# esp32.net
KiCad netlist of a schematic drawn in Altium Designer
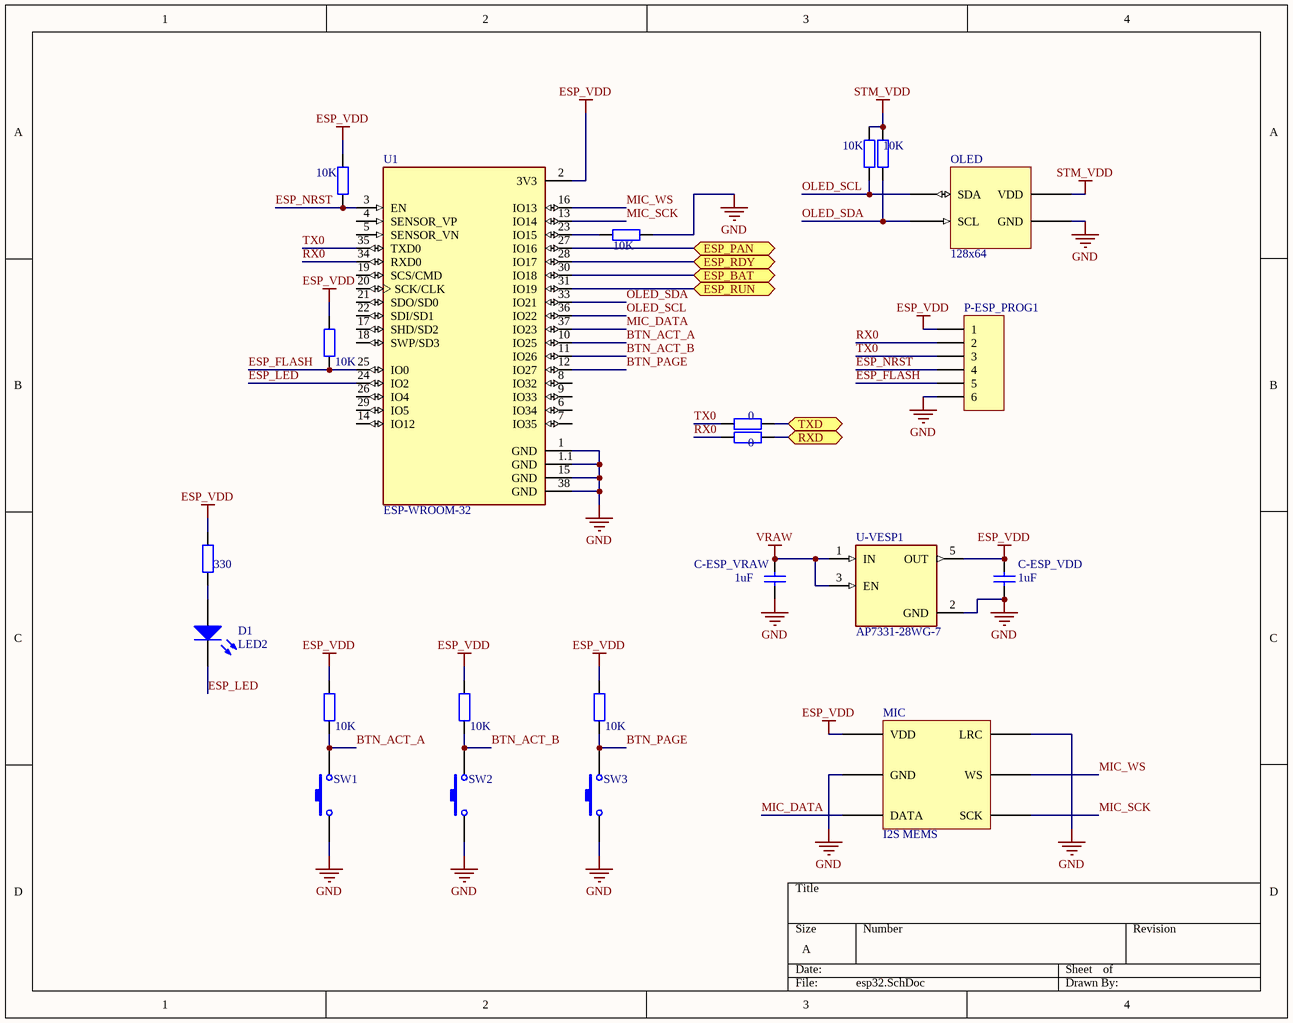
[diagram p0: esp32.SchDoc]

(export (version "E")
  (design (tool "Eeschema 10.0.6"))
  (components
    (comp (ref "C-ESP_VDD")
      (value "1uF")
      (footprint "RAD-0.3")
      (description "Capacitor")
      (fields (field (name "Comment") "Cap") (field (name "PUBLISHER") "Altium Limited"))
      (libsource (lib "Miscellaneous Devices") (part "Cap"))
    )
    (comp (ref "C-ESP_VRAW")
      (value "1uF")
      (footprint "RAD-0.3")
      (description "Capacitor")
      (fields (field (name "Comment") "Cap") (field (name "PUBLISHER") "Altium Limited"))
      (libsource (lib "Miscellaneous Devices") (part "Cap"))
    )
    (comp (ref "D1")
      (value "LED2")
      (footprint "3.2X1.6X1.1")
      (description "Typical RED, GREEN, YELLOW, AMBER GaAs LED")
      (fields (field (name "PUBLISHER") "Altium Limited"))
      (libsource (lib "Miscellaneous Devices") (part "LED2"))
    )
    (comp (ref "MIC") (value "I2S MEMS") (libsource (lib "INMP441") (part "INMP441")))
    (comp (ref "OLED") (value "128x64") (libsource (lib "SH1106") (part "SH1106")))
    (comp (ref "P-ESP_PROG1")
      (value "Header 6")
      (footprint "HDR1X6")
      (description "Header, 6-Pin")
      (fields (field (name "PUBLISHER") "Altium Limited"))
      (libsource (lib "Miscellaneous Connectors") (part "Header 6"))
    )
    (comp (ref "R-BUTTON1")
      (value "10K")
      (footprint "AXIAL-0.4")
      (description "Resistor")
      (fields (field (name "Comment") "Res2") (field (name "PUBLISHER") "Altium Limited"))
      (libsource (lib "Miscellaneous Devices") (part "Res2"))
    )
    (comp (ref "R-BUTTON2")
      (value "10K")
      (footprint "AXIAL-0.4")
      (description "Resistor")
      (fields (field (name "Comment") "Res2") (field (name "PUBLISHER") "Altium Limited"))
      (libsource (lib "Miscellaneous Devices") (part "Res2"))
    )
    (comp (ref "R-BUTTON3")
      (value "10K")
      (footprint "AXIAL-0.4")
      (description "Resistor")
      (fields (field (name "Comment") "Res2") (field (name "PUBLISHER") "Altium Limited"))
      (libsource (lib "Miscellaneous Devices") (part "Res2"))
    )
    (comp (ref "R-ESP-LOG1")
      (value "10K")
      (footprint "AXIAL-0.4")
      (description "Resistor")
      (fields (field (name "Comment") "Res2") (field (name "PUBLISHER") "Altium Limited"))
      (libsource (lib "") (part "Res2_2"))
    )
    (comp (ref "R-ESP1")
      (value "10K")
      (footprint "AXIAL-0.4")
      (description "Resistor")
      (fields (field (name "Comment") "Res2") (field (name "PUBLISHER") "Altium Limited"))
      (libsource (lib "Miscellaneous Devices") (part "Res2"))
    )
    (comp (ref "R-ESP2")
      (value "10K")
      (footprint "AXIAL-0.4")
      (description "Resistor")
      (fields (field (name "Comment") "Res2") (field (name "PUBLISHER") "Altium Limited"))
      (libsource (lib "Miscellaneous Devices") (part "Res2"))
    )
    (comp (ref "R-LED1")
      (value "330")
      (footprint "AXIAL-0.4")
      (description "Resistor")
      (fields (field (name "Comment") "Res2") (field (name "PUBLISHER") "Altium Limited"))
      (libsource (lib "Miscellaneous Devices") (part "Res2"))
    )
    (comp (ref "R-OLED1")
      (value "10K")
      (footprint "AXIAL-0.4")
      (description "Resistor")
      (fields (field (name "Comment") "Res2") (field (name "PUBLISHER") "Altium Limited"))
      (libsource (lib "Miscellaneous Devices") (part "Res2"))
    )
    (comp (ref "R-OLED2")
      (value "10K")
      (footprint "AXIAL-0.4")
      (description "Resistor")
      (fields (field (name "Comment") "Res2") (field (name "PUBLISHER") "Altium Limited"))
      (libsource (lib "Miscellaneous Devices") (part "Res2"))
    )
    (comp (ref "R-UART1")
      (value "0")
      (footprint "AXIAL-0.4")
      (description "Resistor")
      (fields (field (name "Comment") "Res2") (field (name "PUBLISHER") "Altium Limited"))
      (libsource (lib "") (part "Res2_1"))
    )
    (comp (ref "R-UART2")
      (value "0")
      (footprint "AXIAL-0.4")
      (description "Resistor")
      (fields (field (name "Comment") "Res2") (field (name "PUBLISHER") "Altium Limited"))
      (libsource (lib "") (part "Res2_1"))
    )
    (comp (ref "SW1")
      (value "SW-PB")
      (footprint "SPST-2")
      (description "Switch")
      (fields (field (name "PUBLISHER") "Altium Limited"))
      (libsource (lib "Miscellaneous Devices") (part "SW-PB"))
    )
    (comp (ref "SW2")
      (value "SW-PB")
      (footprint "SPST-2")
      (description "Switch")
      (fields (field (name "PUBLISHER") "Altium Limited"))
      (libsource (lib "Miscellaneous Devices") (part "SW-PB"))
    )
    (comp (ref "SW3")
      (value "SW-PB")
      (footprint "SPST-2")
      (description "Switch")
      (fields (field (name "PUBLISHER") "Altium Limited"))
      (libsource (lib "Miscellaneous Devices") (part "SW-PB"))
    )
    (comp (ref "U-VESP1")
      (value "AP7331-28WG-7")
      (footprint "SOT95P285X145-5N")
      (description "Linear Voltage Regulator IC 1 Output 300mA SOT-25")
      (fields (field (name "MF") "Diodes Inc."))
      (libsource (lib "AP7331-28WG-7") (part "AP7331-28WG-7"))
    )
    (comp (ref "U1")
      (value "ESP-WROOM-32")
      (footprint "MODULE_ESP-WROOM-32")
      (description "WiFi 802.11b/g/n/d/e/i Transceiver Module 2.4GHz Surface Mount")
      (fields (field (name "MF") "Olimex LTD"))
      (libsource (lib "ESP-WROOM-32") (part "ESP-WROOM-32"))
    )
  )
  (nets
    (net (code "1") (name "/BTN_ACT_A") (class "Default")
      (node (ref "R-BUTTON1") (pin "1") (pinfunction "1_1") (pintype "passive"))
      (node (ref "SW1") (pin "2") (pinfunction "2_2") (pintype "passive"))
      (node (ref "U1") (pin "10") (pinfunction "IO25_10") (pintype "bidirectional"))
    )
    (net (code "2") (name "/BTN_ACT_B") (class "Default")
      (node (ref "R-BUTTON2") (pin "1") (pinfunction "1_1") (pintype "passive"))
      (node (ref "SW2") (pin "2") (pinfunction "2_2") (pintype "passive"))
      (node (ref "U1") (pin "11") (pinfunction "IO26_11") (pintype "bidirectional"))
    )
    (net (code "3") (name "/BTN_PAGE") (class "Default")
      (node (ref "R-BUTTON3") (pin "1") (pinfunction "1_1") (pintype "passive"))
      (node (ref "SW3") (pin "2") (pinfunction "2_2") (pintype "passive"))
      (node (ref "U1") (pin "12") (pinfunction "IO27_12") (pintype "bidirectional"))
    )
    (net (code "4") (name "/ESP_BAT") (class "Default")
      (node (ref "U1") (pin "30") (pinfunction "IO18_30") (pintype "bidirectional"))
    )
    (net (code "5") (name "/ESP_FLASH") (class "Default")
      (node (ref "P-ESP_PROG1") (pin "5") (pinfunction "5_5") (pintype "passive"))
      (node (ref "R-ESP2") (pin "1") (pinfunction "1_1") (pintype "passive"))
      (node (ref "U1") (pin "25") (pinfunction "IO0_25") (pintype "bidirectional"))
    )
    (net (code "6") (name "/ESP_LED") (class "Default")
      (node (ref "D1") (pin "2") (pinfunction "K_2") (pintype "passive"))
      (node (ref "U1") (pin "24") (pinfunction "IO2_24") (pintype "bidirectional"))
    )
    (net (code "7") (name "/ESP_NRST") (class "Default")
      (node (ref "P-ESP_PROG1") (pin "4") (pinfunction "4_4") (pintype "passive"))
      (node (ref "R-ESP1") (pin "1") (pinfunction "1_1") (pintype "passive"))
      (node (ref "U1") (pin "3") (pinfunction "EN_3") (pintype "input"))
    )
    (net (code "8") (name "/ESP_PAN") (class "Default")
      (node (ref "U1") (pin "27") (pinfunction "IO16_27") (pintype "bidirectional"))
    )
    (net (code "9") (name "/ESP_RDY") (class "Default")
      (node (ref "U1") (pin "28") (pinfunction "IO17_28") (pintype "bidirectional"))
    )
    (net (code "10") (name "/ESP_RUN") (class "Default")
      (node (ref "U1") (pin "31") (pinfunction "IO19_31") (pintype "bidirectional"))
    )
    (net (code "11") (name "/MIC_DATA") (class "Default")
      (node (ref "MIC") (pin "DATA") (pinfunction "DATA_DATA") (pintype "passive"))
      (node (ref "U1") (pin "37") (pinfunction "IO23_37") (pintype "bidirectional"))
    )
    (net (code "12") (name "/MIC_SCK") (class "Default")
      (node (ref "MIC") (pin "SCK") (pinfunction "SCK_SCK") (pintype "passive"))
      (node (ref "U1") (pin "13") (pinfunction "IO14_13") (pintype "bidirectional"))
    )
    (net (code "13") (name "/MIC_WS") (class "Default")
      (node (ref "MIC") (pin "WS") (pinfunction "WS_WS") (pintype "passive"))
      (node (ref "U1") (pin "16") (pinfunction "IO13_16") (pintype "bidirectional"))
    )
    (net (code "14") (name "/OLED_SCL") (class "Default")
      (node (ref "OLED") (pin "SDA") (pinfunction "SDA_SDA") (pintype "bidirectional"))
      (node (ref "R-OLED2") (pin "1") (pinfunction "1_1") (pintype "passive"))
      (node (ref "U1") (pin "36") (pinfunction "IO22_36") (pintype "bidirectional"))
    )
    (net (code "15") (name "/OLED_SDA") (class "Default")
      (node (ref "OLED") (pin "SCL") (pinfunction "SCL_SCL") (pintype "input"))
      (node (ref "R-OLED1") (pin "1") (pinfunction "1_1") (pintype "passive"))
      (node (ref "U1") (pin "33") (pinfunction "IO21_33") (pintype "bidirectional"))
    )
    (net (code "16") (name "/RX0") (class "Default")
      (node (ref "P-ESP_PROG1") (pin "2") (pinfunction "2_2") (pintype "passive"))
      (node (ref "R-UART2") (pin "1") (pinfunction "1_1") (pintype "passive"))
      (node (ref "U1") (pin "34") (pinfunction "RXD0_34") (pintype "bidirectional"))
    )
    (net (code "17") (name "/RXD") (class "Default")
      (node (ref "R-UART2") (pin "2") (pinfunction "2_2") (pintype "passive"))
    )
    (net (code "18") (name "/TX0") (class "Default")
      (node (ref "P-ESP_PROG1") (pin "3") (pinfunction "3_3") (pintype "passive"))
      (node (ref "R-UART1") (pin "1") (pinfunction "1_1") (pintype "passive"))
      (node (ref "U1") (pin "35") (pinfunction "TXD0_35") (pintype "bidirectional"))
    )
    (net (code "19") (name "/TXD") (class "Default")
      (node (ref "R-UART1") (pin "2") (pinfunction "2_2") (pintype "passive"))
    )
    (net (code "20") (name "ESP_VDD") (class "Default")
      (node (ref "C-ESP_VDD") (pin "2") (pinfunction "2_2") (pintype "passive"))
      (node (ref "MIC") (pin "VDD") (pinfunction "VDD_VDD") (pintype "power_in"))
      (node (ref "P-ESP_PROG1") (pin "1") (pinfunction "1_1") (pintype "passive"))
      (node (ref "R-BUTTON1") (pin "2") (pinfunction "2_2") (pintype "passive"))
      (node (ref "R-BUTTON2") (pin "2") (pinfunction "2_2") (pintype "passive"))
      (node (ref "R-BUTTON3") (pin "2") (pinfunction "2_2") (pintype "passive"))
      (node (ref "R-ESP1") (pin "2") (pinfunction "2_2") (pintype "passive"))
      (node (ref "R-ESP2") (pin "2") (pinfunction "2_2") (pintype "passive"))
      (node (ref "R-LED1") (pin "2") (pinfunction "2_2") (pintype "passive"))
      (node (ref "U-VESP1") (pin "5") (pinfunction "OUT_5") (pintype "output"))
      (node (ref "U1") (pin "2") (pinfunction "3V3_2") (pintype "power_in"))
    )
    (net (code "21") (name "GND") (class "Default")
      (node (ref "C-ESP_VDD") (pin "1") (pinfunction "1_1") (pintype "passive"))
      (node (ref "C-ESP_VRAW") (pin "1") (pinfunction "1_1") (pintype "passive"))
      (node (ref "MIC") (pin "GND") (pinfunction "GND_GND") (pintype "power_in"))
      (node (ref "MIC") (pin "LRC") (pinfunction "LRC_LRC") (pintype "passive"))
      (node (ref "OLED") (pin "GND") (pinfunction "GND_GND") (pintype "power_in"))
      (node (ref "P-ESP_PROG1") (pin "6") (pinfunction "6_6") (pintype "passive"))
      (node (ref "R-ESP-LOG1") (pin "1") (pinfunction "1_1") (pintype "passive"))
      (node (ref "SW1") (pin "1") (pinfunction "1_1") (pintype "passive"))
      (node (ref "SW2") (pin "1") (pinfunction "1_1") (pintype "passive"))
      (node (ref "SW3") (pin "1") (pinfunction "1_1") (pintype "passive"))
      (node (ref "U-VESP1") (pin "2") (pinfunction "GND_2") (pintype "power_in"))
      (node (ref "U1") (pin "1") (pinfunction "GND_1") (pintype "power_in"))
      (node (ref "U1") (pin "1.1") (pinfunction "GND_1.1") (pintype "power_in"))
      (node (ref "U1") (pin "15") (pinfunction "GND_15") (pintype "power_in"))
      (node (ref "U1") (pin "38") (pinfunction "GND_38") (pintype "power_in"))
    )
    (net (code "22") (name "Net-(D1-A)") (class "Default")
      (node (ref "D1") (pin "1") (pinfunction "A_1") (pintype "passive"))
      (node (ref "R-LED1") (pin "1") (pinfunction "1_1") (pintype "passive"))
    )
    (net (code "23") (name "Net-(U1-IO15)") (class "Default")
      (node (ref "R-ESP-LOG1") (pin "2") (pinfunction "2_2") (pintype "passive"))
      (node (ref "U1") (pin "23") (pinfunction "IO15_23") (pintype "bidirectional"))
    )
    (net (code "24") (name "STM_VDD") (class "Default")
      (node (ref "OLED") (pin "VDD") (pinfunction "VDD_VDD") (pintype "power_in"))
      (node (ref "R-OLED1") (pin "2") (pinfunction "2_2") (pintype "passive"))
      (node (ref "R-OLED2") (pin "2") (pinfunction "2_2") (pintype "passive"))
    )
    (net (code "25") (name "VRAW") (class "Default")
      (node (ref "C-ESP_VRAW") (pin "2") (pinfunction "2_2") (pintype "passive"))
      (node (ref "U-VESP1") (pin "1") (pinfunction "IN_1") (pintype "input"))
      (node (ref "U-VESP1") (pin "3") (pinfunction "EN_3") (pintype "input"))
    )
    (net (code "26") (name "unconnected-(U1-IO4-Pad26)") (class "Default")
      (node (ref "U1") (pin "26") (pinfunction "IO4_26") (pintype "bidirectional"))
    )
    (net (code "27") (name "unconnected-(U1-IO5-Pad29)") (class "Default")
      (node (ref "U1") (pin "29") (pinfunction "IO5_29") (pintype "bidirectional"))
    )
    (net (code "28") (name "unconnected-(U1-IO12-Pad14)") (class "Default")
      (node (ref "U1") (pin "14") (pinfunction "IO12_14") (pintype "bidirectional"))
    )
    (net (code "29") (name "unconnected-(U1-IO32-Pad8)") (class "Default")
      (node (ref "U1") (pin "8") (pinfunction "IO32_8") (pintype "bidirectional"))
    )
    (net (code "30") (name "unconnected-(U1-IO33-Pad9)") (class "Default")
      (node (ref "U1") (pin "9") (pinfunction "IO33_9") (pintype "bidirectional"))
    )
    (net (code "31") (name "unconnected-(U1-IO34-Pad6)") (class "Default")
      (node (ref "U1") (pin "6") (pinfunction "IO34_6") (pintype "bidirectional"))
    )
    (net (code "32") (name "unconnected-(U1-IO35-Pad7)") (class "Default")
      (node (ref "U1") (pin "7") (pinfunction "IO35_7") (pintype "bidirectional"))
    )
    (net (code "33") (name "unconnected-(U1-SCK{slash}CLK-Pad20)") (class "Default")
      (node (ref "U1") (pin "20") (pinfunction "SCK/CLK_20") (pintype "bidirectional"))
    )
    (net (code "34") (name "unconnected-(U1-SCS{slash}CMD-Pad19)") (class "Default")
      (node (ref "U1") (pin "19") (pinfunction "SCS/CMD_19") (pintype "bidirectional"))
    )
    (net (code "35") (name "unconnected-(U1-SDI{slash}SD1-Pad22)") (class "Default")
      (node (ref "U1") (pin "22") (pinfunction "SDI/SD1_22") (pintype "bidirectional"))
    )
    (net (code "36") (name "unconnected-(U1-SDO{slash}SD0-Pad21)") (class "Default")
      (node (ref "U1") (pin "21") (pinfunction "SDO/SD0_21") (pintype "bidirectional"))
    )
    (net (code "37") (name "unconnected-(U1-SENSOR_VN-Pad5)") (class "Default")
      (node (ref "U1") (pin "5") (pinfunction "SENSOR_VN_5") (pintype "input"))
    )
    (net (code "38") (name "unconnected-(U1-SENSOR_VP-Pad4)") (class "Default")
      (node (ref "U1") (pin "4") (pinfunction "SENSOR_VP_4") (pintype "input"))
    )
    (net (code "39") (name "unconnected-(U1-SHD{slash}SD2-Pad17)") (class "Default")
      (node (ref "U1") (pin "17") (pinfunction "SHD/SD2_17") (pintype "bidirectional"))
    )
    (net (code "40") (name "unconnected-(U1-SWP{slash}SD3-Pad18)") (class "Default")
      (node (ref "U1") (pin "18") (pinfunction "SWP/SD3_18") (pintype "bidirectional"))
    )
  )
)
